# CanTrans.net
KiCad netlist of a schematic drawn in Altium Designer
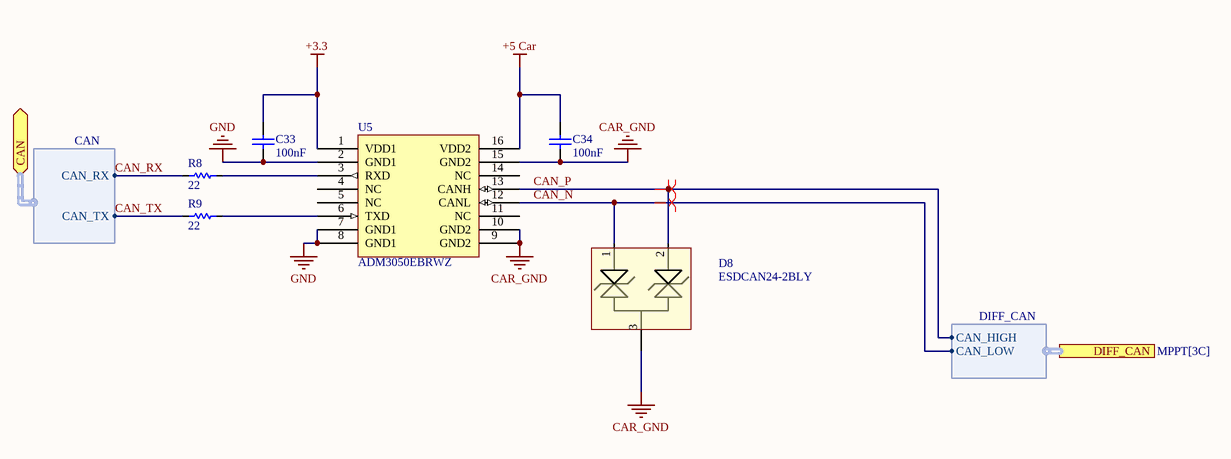
[diagram p0: CanTrans.SchDoc]

(export (version "E")
  (design (tool "Eeschema 10.0.6"))
  (components
    (comp (ref "C33")
      (value "100nF")
      (footprint "CAPC1608X90X40ML10T20")
      (description "Chip Capacitor, 0.1uF, +/- 10%, 50 V, 0603 (1608 Metric)")
      (fields (field (name "TOLERANCE") "10%") (field (name "Comment") "Capacitor 0.1uF +/-10% 50 V 0603"))
      (libsource (lib "University of Minnesota - Solar Vehicle Project") (part "Cap"))
    )
    (comp (ref "C34")
      (value "100nF")
      (footprint "CAPC1608X90X40ML10T20")
      (description "Chip Capacitor, 0.1uF, +/- 10%, 50 V, 0603 (1608 Metric)")
      (fields (field (name "TOLERANCE") "10%") (field (name "Comment") "Capacitor 0.1uF +/-10% 50 V 0603"))
      (libsource (lib "University of Minnesota - Solar Vehicle Project") (part "Cap"))
    )
    (comp (ref "D8")
      (value "ESDCAN24-2BLY")
      (footprint "SOT23-3")
      (description "ESD Suppressor TVS 24V Automotive 3-Pin SOT-23 T/R")
      (libsource (lib "University of Minnesota - Solar Vehicle Project") (part "D_MMBZ6V8AL,215"))
    )
    (comp (ref "R8")
      (value "22")
      (footprint "0603_RESISTOR")
      (description "RES 22 OHM 1/16W 1% 0603 SMD")
      (fields (field (name "TOLERANCE") "1%") (field (name "POWER") "62.5mW"))
      (libsource (lib "University of Minnesota - Solar Vehicle Project") (part "Symbol"))
    )
    (comp (ref "R9")
      (value "22")
      (footprint "0603_RESISTOR")
      (description "RES 22 OHM 1/16W 1% 0603 SMD")
      (fields (field (name "TOLERANCE") "1%") (field (name "POWER") "62.5mW"))
      (libsource (lib "University of Minnesota - Solar Vehicle Project") (part "Symbol"))
    )
    (comp (ref "U5")
      (value "ADM3050EBRWZ")
      (footprint "SOIC127P1030X265-16N")
      (description "MIL-STD-1553 Data Bus Transceiver, PDSO16. Isolated CANFD transceiver")
      (libsource (lib "University of Minnesota - Solar Vehicle Project") (part "ADM3050EBRWZ-Symbol-1"))
    )
  )
  (nets
    (net (code "3") (name "+3.3") (class "Default")
      (node (ref "C33") (pin "2") (pinfunction "2_2") (pintype "passive"))
      (node (ref "U5") (pin "1") (pinfunction "VDD1_1") (pintype "power_in"))
    )
    (net (code "4") (name "+5 Car") (class "Default")
      (node (ref "C34") (pin "1") (pinfunction "1_1") (pintype "passive"))
      (node (ref "U5") (pin "16") (pinfunction "VDD2_16") (pintype "power_in"))
    )
    (net (code "5") (name "/CAN_N") (class "Default")
      (node (ref "D8") (pin "1") (pinfunction "1_1") (pintype "passive"))
      (node (ref "U5") (pin "12") (pinfunction "CANL_12") (pintype "bidirectional"))
    )
    (net (code "6") (name "/CAN_P") (class "Default")
      (node (ref "D8") (pin "2") (pinfunction "2_2") (pintype "passive"))
      (node (ref "U5") (pin "13") (pinfunction "CANH_13") (pintype "bidirectional"))
    )
    (net (code "7") (name "/CAN_RX") (class "Default")
      (node (ref "R8") (pin "1") (pinfunction "1_1") (pintype "passive"))
    )
    (net (code "8") (name "/CAN_TX") (class "Default")
      (node (ref "R9") (pin "1") (pinfunction "1_1") (pintype "passive"))
    )
    (net (code "11") (name "CAR_GND") (class "Default")
      (node (ref "C34") (pin "2") (pinfunction "2_2") (pintype "passive"))
      (node (ref "D8") (pin "3") (pinfunction "3_3") (pintype "passive"))
      (node (ref "U5") (pin "10") (pinfunction "GND2_10") (pintype "power_in"))
      (node (ref "U5") (pin "15") (pinfunction "GND2_15") (pintype "power_in"))
      (node (ref "U5") (pin "9") (pinfunction "GND2_9") (pintype "power_in"))
    )
    (net (code "12") (name "GND") (class "Default")
      (node (ref "C33") (pin "1") (pinfunction "1_1") (pintype "passive"))
      (node (ref "U5") (pin "2") (pinfunction "GND1_2") (pintype "power_in"))
      (node (ref "U5") (pin "7") (pinfunction "GND1_7") (pintype "power_in"))
      (node (ref "U5") (pin "8") (pinfunction "GND1_8") (pintype "power_in"))
    )
    (net (code "13") (name "Net-(U5-RXD)") (class "Default")
      (node (ref "R8") (pin "2") (pinfunction "2_2") (pintype "passive"))
      (node (ref "U5") (pin "3") (pinfunction "RXD_3") (pintype "output"))
    )
    (net (code "14") (name "Net-(U5-TXD)") (class "Default")
      (node (ref "R9") (pin "2") (pinfunction "2_2") (pintype "passive"))
      (node (ref "U5") (pin "6") (pinfunction "TXD_6") (pintype "input"))
    )
    (net (code "15") (name "unconnected-(U5-NC-Pad4)") (class "Default")
      (node (ref "U5") (pin "4") (pinfunction "NC_4") (pintype "passive"))
    )
    (net (code "16") (name "unconnected-(U5-NC-Pad5)") (class "Default")
      (node (ref "U5") (pin "5") (pinfunction "NC_5") (pintype "passive"))
    )
    (net (code "17") (name "unconnected-(U5-NC-Pad11)") (class "Default")
      (node (ref "U5") (pin "11") (pinfunction "NC_11") (pintype "passive"))
    )
    (net (code "18") (name "unconnected-(U5-NC-Pad14)") (class "Default")
      (node (ref "U5") (pin "14") (pinfunction "NC_14") (pintype "passive"))
    )
  )
)
